# AYDINLATMA_MODUL.net
KiCad netlist of a schematic drawn in EAGLE
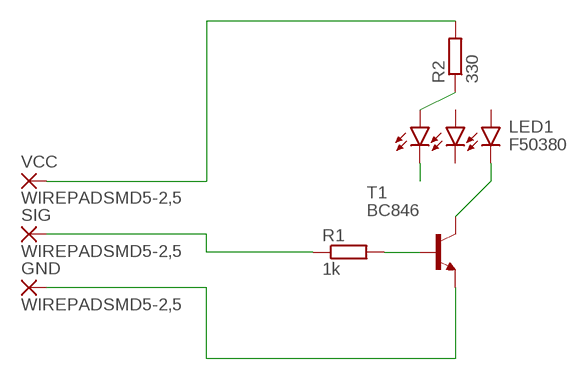
[diagram p0: schematic, sheet 1]

(export (version "E")
  (design (tool "Eeschema 10.0.6"))
  (components
    (comp (ref "GND")
      (value "WIREPADSMD5-2,5")
      (footprint "eagle-import:5-2,5")
      (libsource (lib "eagle-import") (part "WIREPADSMD5-2,5"))
    )
    (comp (ref "LED1")
      (value "F50380")
      (footprint "eagle-import:F50380")
      (libsource (lib "eagle-import") (part "F50380"))
    )
    (comp (ref "R1")
      (value "1k")
      (footprint "eagle-import:R0805")
      (libsource (lib "eagle-import") (part "R-EU_R0805"))
    )
    (comp (ref "R2")
      (value "330")
      (footprint "eagle-import:R0805")
      (libsource (lib "eagle-import") (part "R-EU_R0805"))
    )
    (comp (ref "SIG")
      (value "WIREPADSMD5-2,5")
      (footprint "eagle-import:5-2,5")
      (libsource (lib "eagle-import") (part "WIREPADSMD5-2,5"))
    )
    (comp (ref "T1")
      (value "BC846")
      (footprint "eagle-import:SOT23")
      (libsource (lib "eagle-import") (part "BC846"))
    )
    (comp (ref "VCC")
      (value "WIREPADSMD5-2,5")
      (footprint "eagle-import:5-2,5")
      (libsource (lib "eagle-import") (part "WIREPADSMD5-2,5"))
    )
  )
  (nets
    (net (code "1") (name "Net-(GND-P)") (class "Default")
      (node (ref "GND") (pin "1") (pinfunction "P_1") (pintype "passive"))
      (node (ref "T1") (pin "2") (pinfunction "E_2") (pintype "passive"))
    )
    (net (code "2") (name "Net-(LED1-PadB+)") (class "Default")
      (node (ref "LED1") (pin "B+") (pinfunction "B+_B+") (pintype "passive"))
      (node (ref "R2") (pin "1") (pinfunction "1_1") (pintype "passive"))
    )
    (net (code "3") (name "Net-(SIG-P)") (class "Default")
      (node (ref "R1") (pin "1") (pinfunction "1_1") (pintype "passive"))
      (node (ref "SIG") (pin "1") (pinfunction "P_1") (pintype "passive"))
    )
    (net (code "4") (name "Net-(T1-B)") (class "Default")
      (node (ref "R1") (pin "2") (pinfunction "2_2") (pintype "passive"))
      (node (ref "T1") (pin "1") (pinfunction "B_1") (pintype "passive"))
    )
    (net (code "5") (name "Net-(T1-C)") (class "Default")
      (node (ref "LED1") (pin "R-") (pinfunction "R-_R-") (pintype "passive"))
      (node (ref "T1") (pin "3") (pinfunction "C_3") (pintype "passive"))
    )
    (net (code "6") (name "Net-(VCC-P)") (class "Default")
      (node (ref "R2") (pin "2") (pinfunction "2_2") (pintype "passive"))
      (node (ref "VCC") (pin "1") (pinfunction "P_1") (pintype "passive"))
    )
    (net (code "7") (name "unconnected-(LED1-PadB-)") (class "Default")
      (node (ref "LED1") (pin "B-") (pinfunction "B-_B-") (pintype "passive"))
    )
    (net (code "8") (name "unconnected-(LED1-PadG+)") (class "Default")
      (node (ref "LED1") (pin "G+") (pinfunction "G+_G+") (pintype "passive"))
    )
    (net (code "9") (name "unconnected-(LED1-PadG-)") (class "Default")
      (node (ref "LED1") (pin "G-") (pinfunction "G-_G-") (pintype "passive"))
    )
    (net (code "10") (name "unconnected-(LED1-PadR+)") (class "Default")
      (node (ref "LED1") (pin "R+") (pinfunction "R+_R+") (pintype "passive"))
    )
  )
)
